# design.net
KiCad netlist of a schematic drawn in EasyEDA Pro
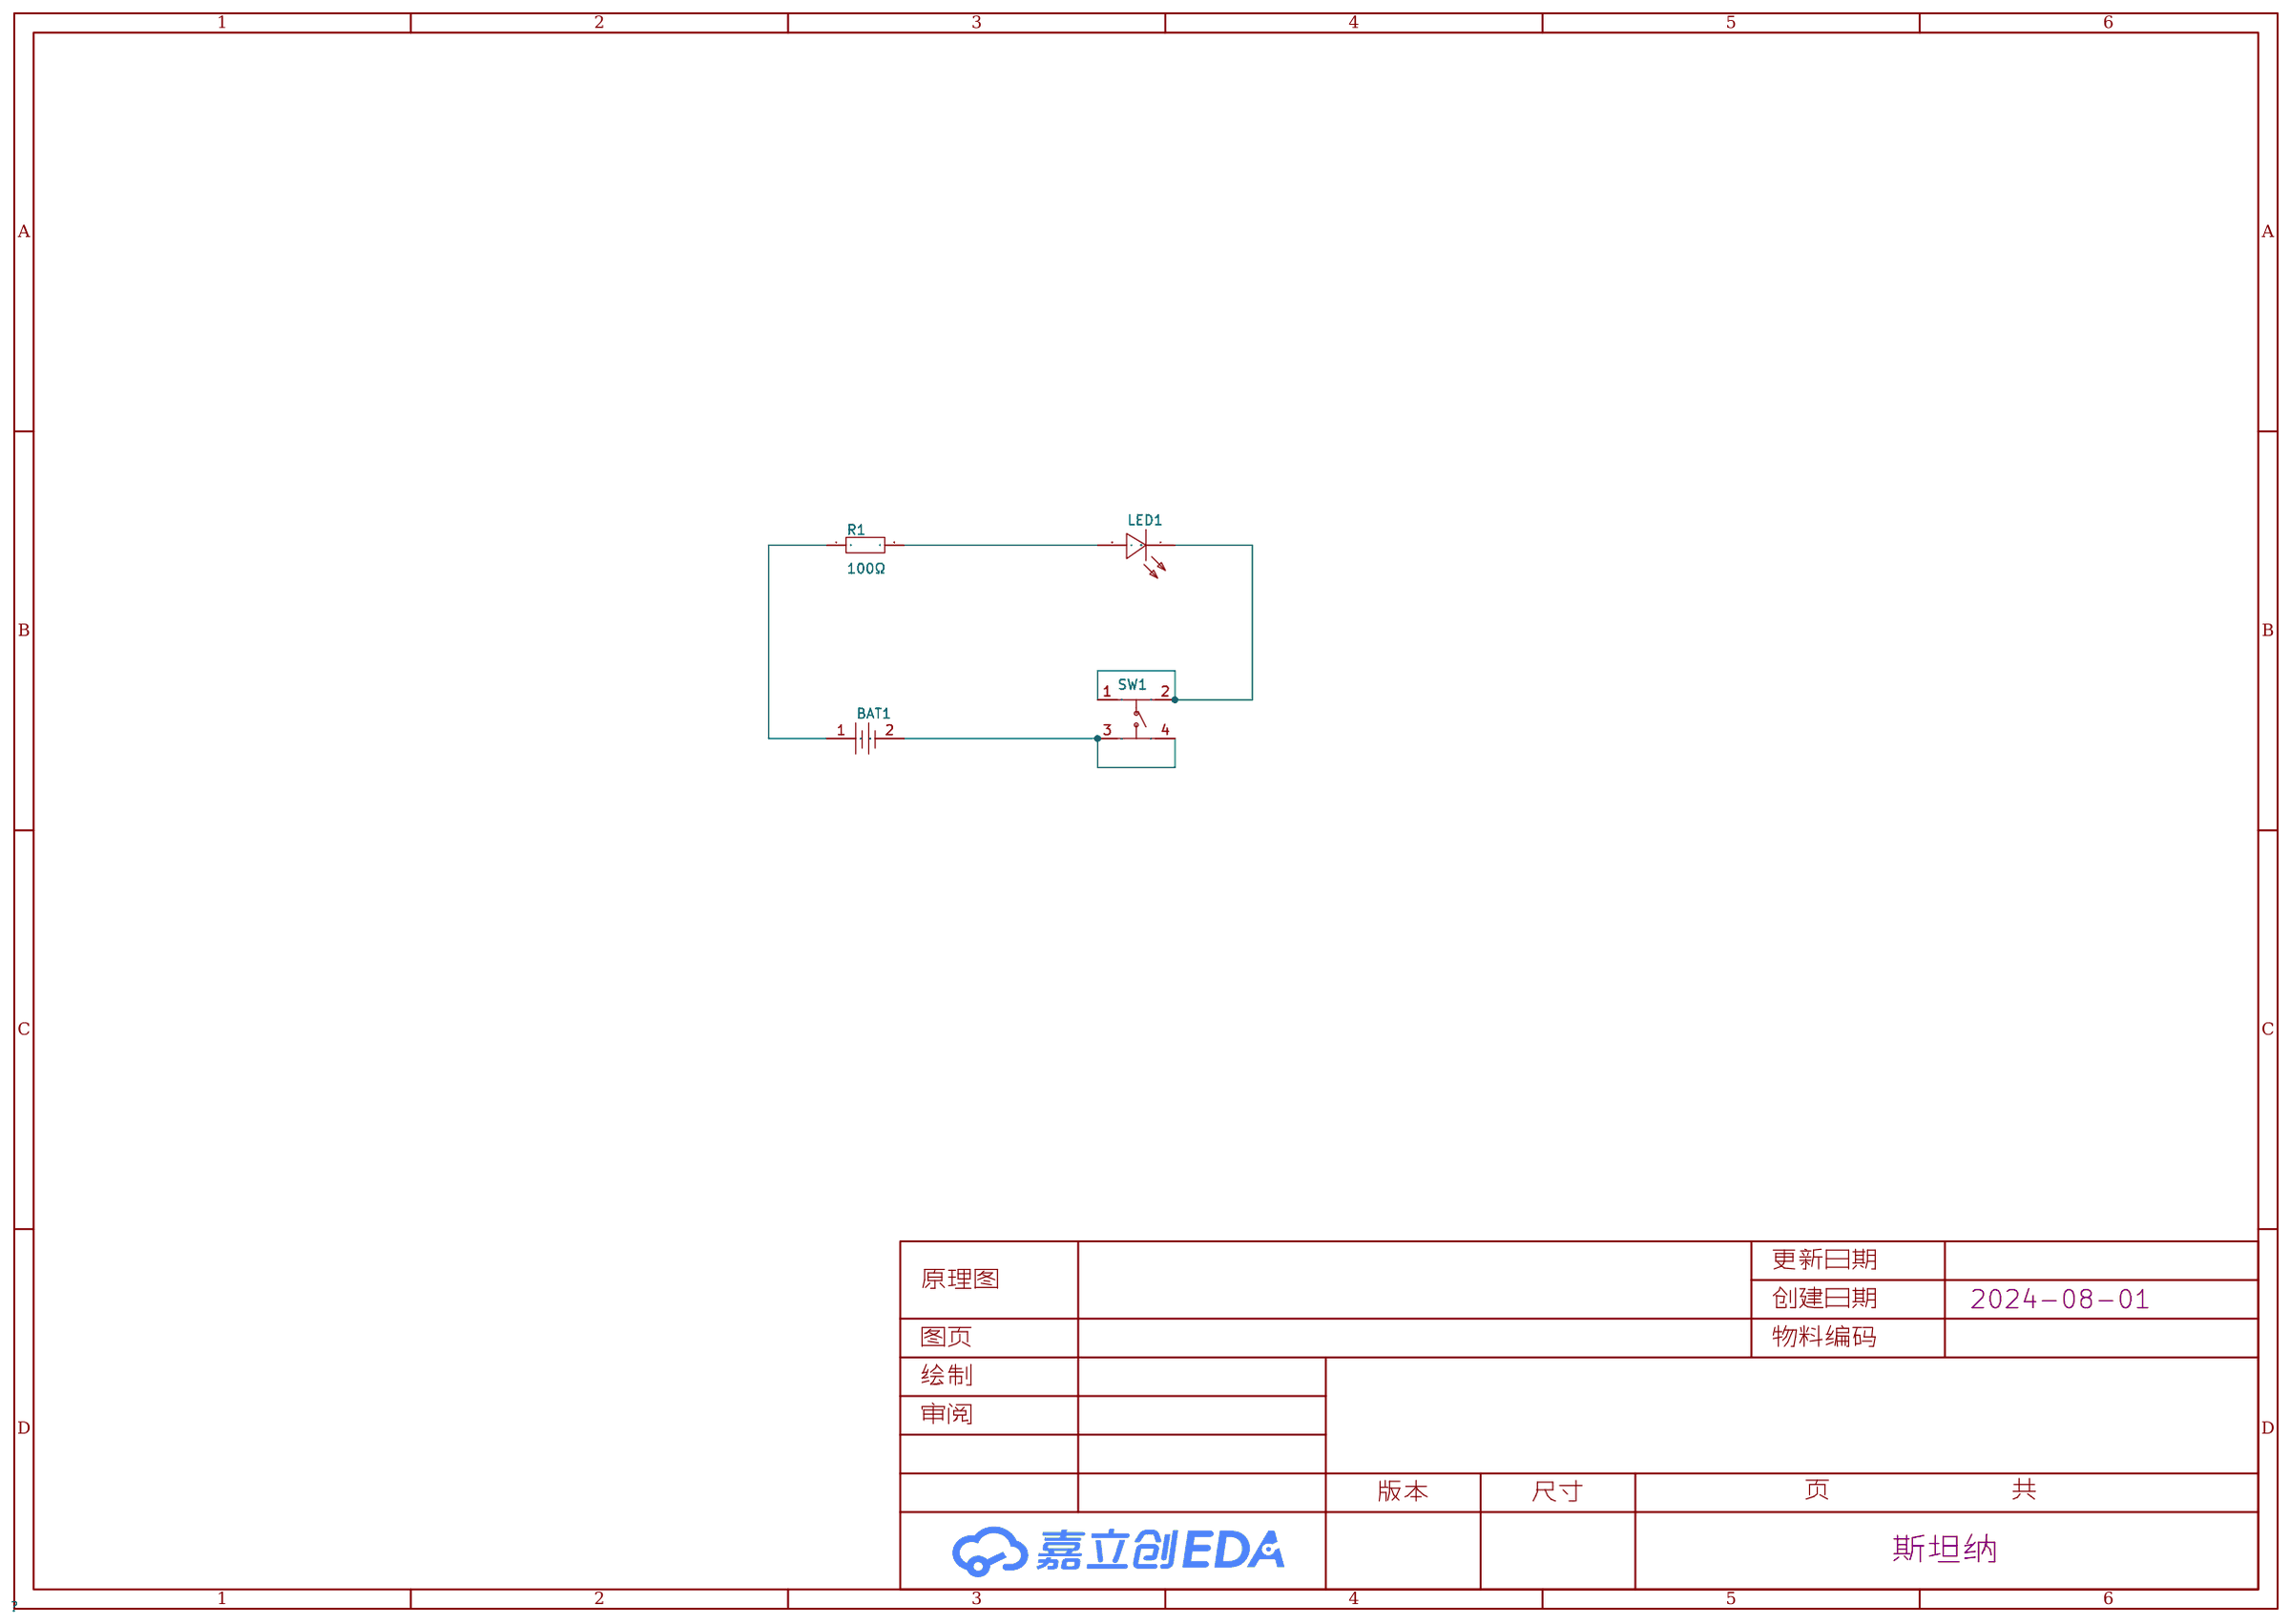
[diagram p0: schematic sheet]

(export (version "E")
  (design (tool "Eeschema 10.0.6"))
  (components
    (comp (ref "BAT1")
      (value "KH-CR2032-2-1")
      (footprint "easyedapro:BAT-TH_KH-CR2032-2-1")
      (description "B-2-1环保1号模 铜(加强版)")
      (fields (field (name "Manufacturer") "kinghelm(金航标)"))
      (libsource (lib "easyedapro") (part "KH-CR2032-2-1"))
    )
    (comp (ref "LED1")
      (value "204-10SDRD/S530-A3/F182-68")
      (footprint "easyedapro:LED-TH_BD4.0-P2.50-RD")
      (fields (field (name "Manufacturer") "EVERLIGHT(亿光)"))
      (libsource (lib "easyedapro") (part "204-10SDRD/S530-A3/F182-68"))
    )
    (comp (ref "R1")
      (value "100Ω")
      (footprint "easyedapro:RES-TH_BD2.2-L6.5-P10.50-D0.6")
      (description "电阻类型:金属膜电阻;阻值:100Ω;精度:±1%;功率:250mW;温度系数:±50ppm/°C;")
      (fields
        (field (name "Manufacturer Part") "MFR0W4F1000A50")
        (field (name "Manufacturer") "UNI-ROYAL(厚声)")
      )
      (libsource (lib "easyedapro") (part "MFR0W4F1000A50"))
    )
    (comp (ref "SW1")
      (value "KH-6X6X5H-STM")
      (footprint "easyedapro:SW-SMD_4P-L6.0-W6.0-P4.50-LS9.0-2")
      (description "电路结构:单刀单掷;按钮形状:圆形按钮;安装方式:立贴;开关长度:6mm;开关宽度:6mm;开关高度:5mm;带支架:不带;触点电流:50mA;额定电压(DC):12V;机械寿命:8万次;")
      (fields (field (name "Manufacturer") "kinghelm(金航标)"))
      (libsource (lib "easyedapro") (part "KH-6X6X5H-STM"))
    )
  )
  (nets
    (net (code "1") (name "Net-(BAT1-Pad1)") (class "Default")
      (node (ref "BAT1") (pin "1") (pinfunction "1_1") (pintype "input"))
      (node (ref "R1") (pin "1") (pinfunction "1_1") (pintype "input"))
    )
    (net (code "2") (name "Net-(BAT1-Pad2)") (class "Default")
      (node (ref "BAT1") (pin "2") (pinfunction "2_2") (pintype "input"))
      (node (ref "SW1") (pin "3") (pinfunction "3_3") (pintype "unspecified"))
      (node (ref "SW1") (pin "4") (pinfunction "4_4") (pintype "unspecified"))
    )
    (net (code "3") (name "Net-(LED1-A)") (class "Default")
      (node (ref "LED1") (pin "2") (pinfunction "A_2") (pintype "unspecified"))
      (node (ref "R1") (pin "2") (pinfunction "2_2") (pintype "input"))
    )
    (net (code "4") (name "Net-(LED1-C)") (class "Default")
      (node (ref "LED1") (pin "1") (pinfunction "C_1") (pintype "unspecified"))
      (node (ref "SW1") (pin "1") (pinfunction "1_1") (pintype "unspecified"))
      (node (ref "SW1") (pin "2") (pinfunction "2_2") (pintype "unspecified"))
    )
  )
)
